# Motor_Driver.net
KiCad netlist of a schematic drawn in EAGLE
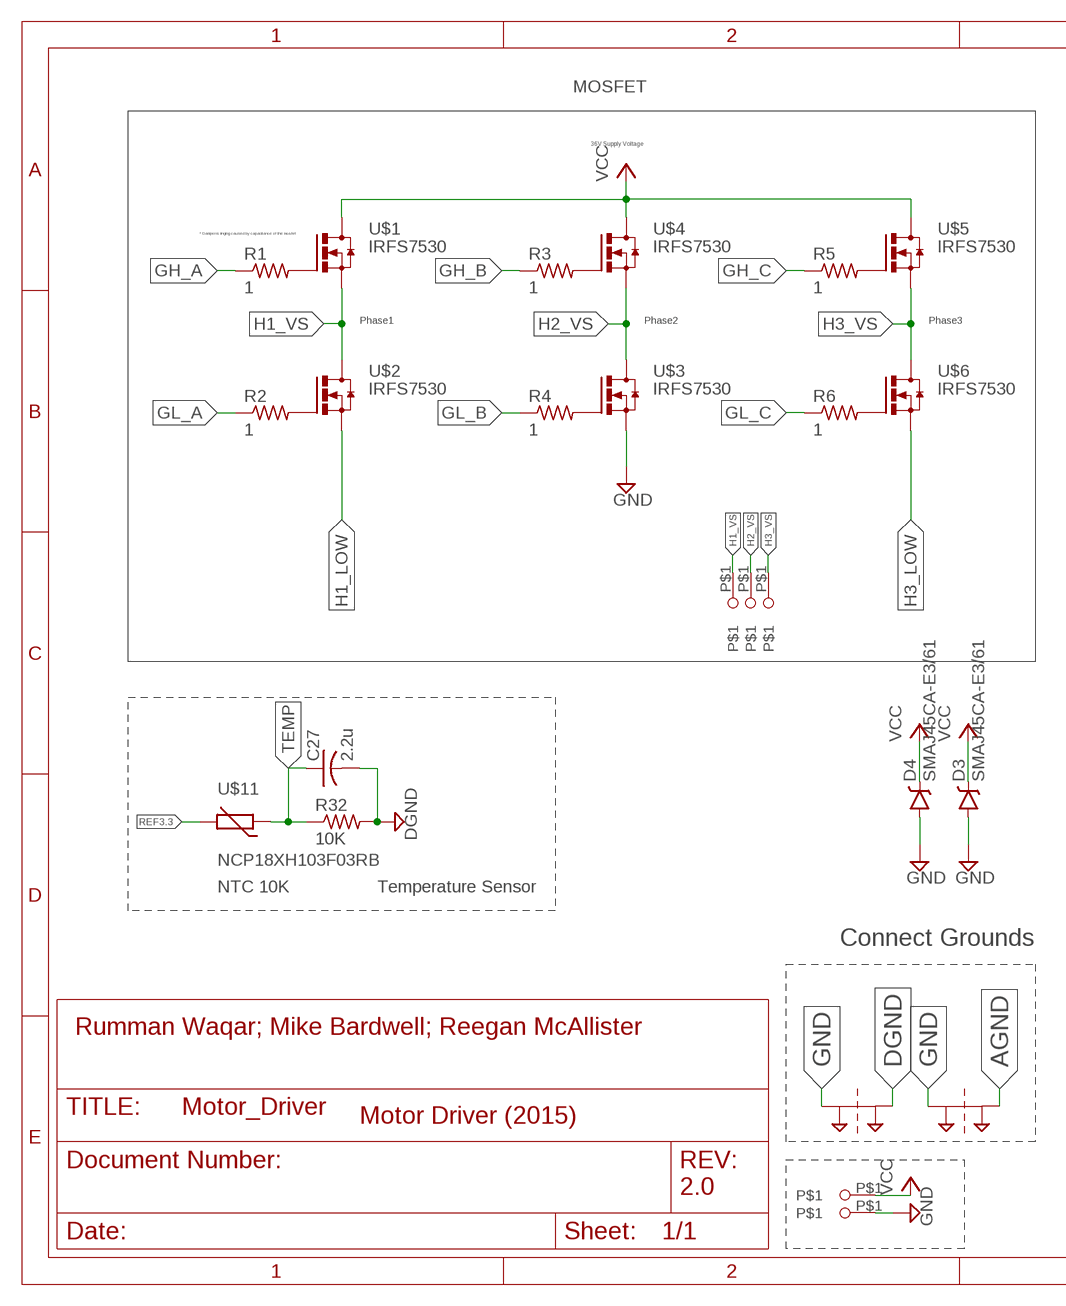
[diagram p0: schematic, sheet 1, part 1 of 2]
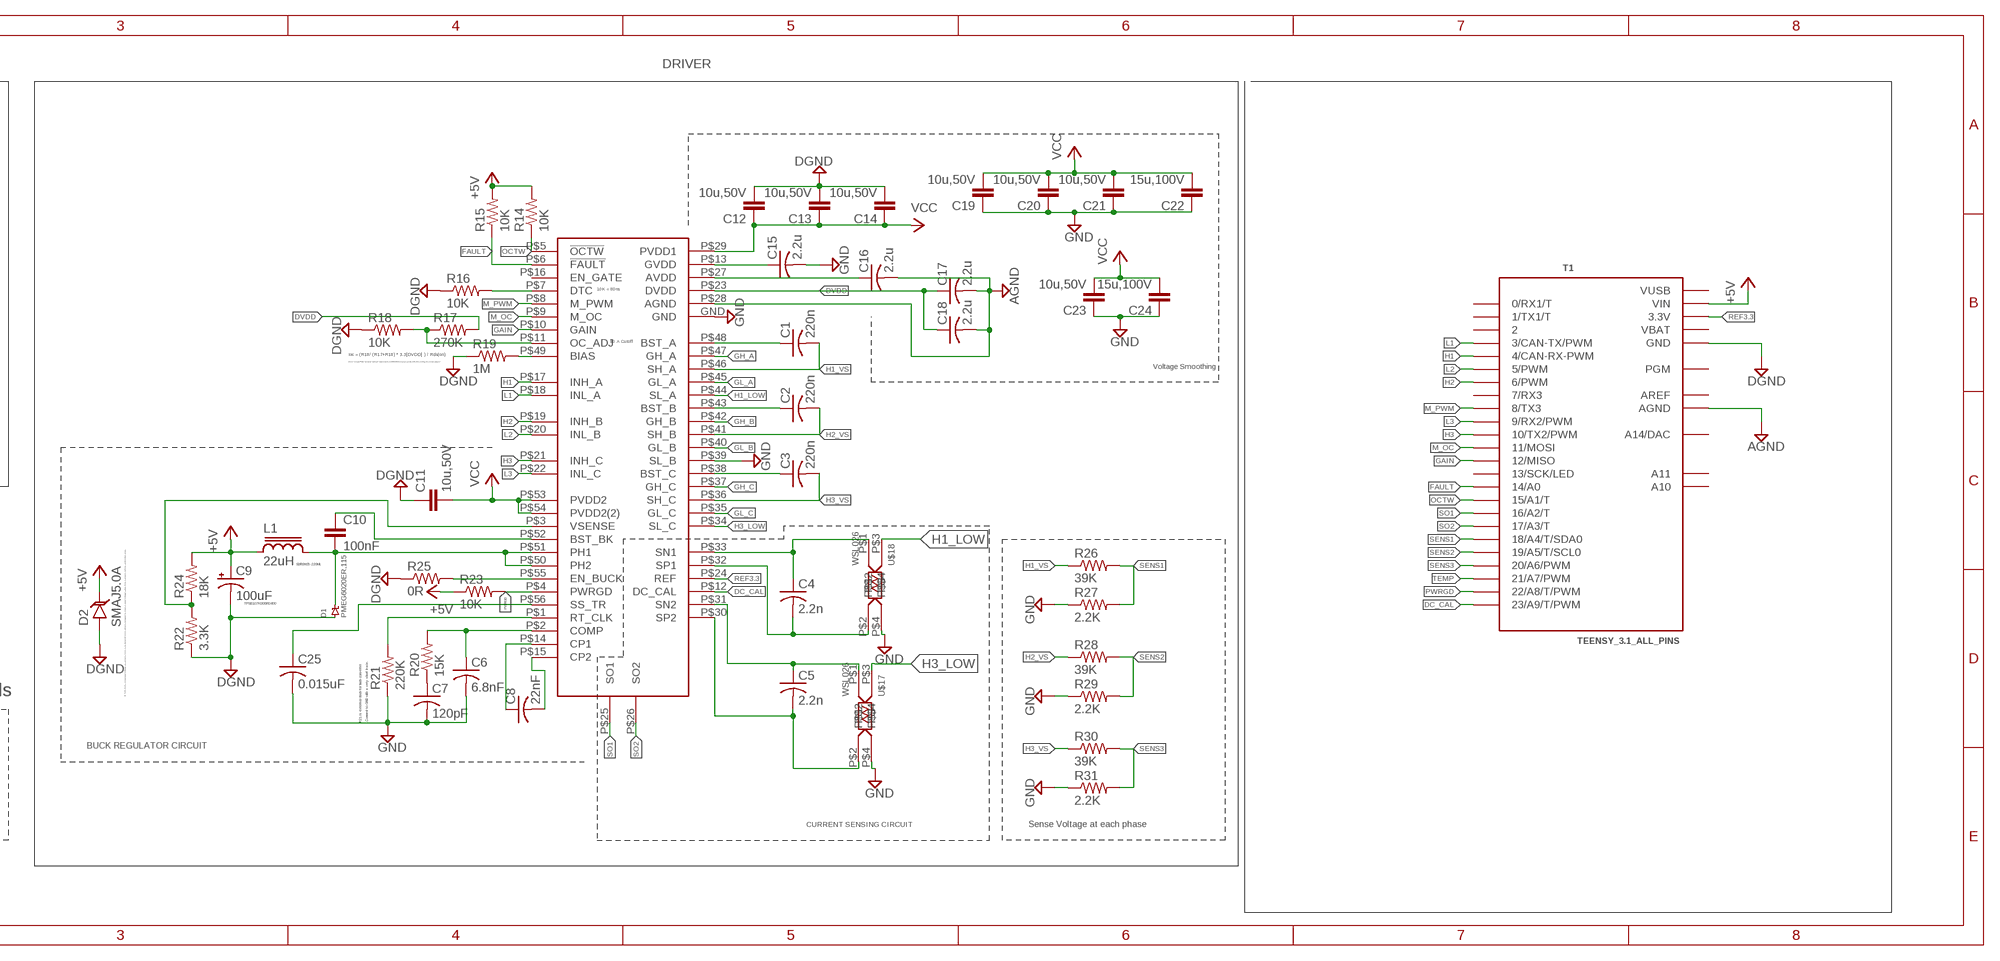
[diagram p1: schematic, sheet 1, part 2 of 2]

(export (version "E")
  (design (tool "Eeschema 10.0.6"))
  (components
    (comp (ref "C1")
      (value "220n")
      (footprint "eagle-import:C0603")
      (libsource (lib "eagle-import") (part "C-USC0603"))
    )
    (comp (ref "C2")
      (value "220n")
      (footprint "eagle-import:C0603")
      (libsource (lib "eagle-import") (part "C-USC0603"))
    )
    (comp (ref "C3")
      (value "220n")
      (footprint "eagle-import:C0603")
      (libsource (lib "eagle-import") (part "C-USC0603"))
    )
    (comp (ref "C4")
      (value "2.2n")
      (footprint "eagle-import:C0603")
      (libsource (lib "eagle-import") (part "C-USC0603"))
    )
    (comp (ref "C5")
      (value "2.2n")
      (footprint "eagle-import:C0603")
      (libsource (lib "eagle-import") (part "C-USC0603"))
    )
    (comp (ref "C6")
      (value "6.8nF")
      (footprint "eagle-import:C0603")
      (libsource (lib "eagle-import") (part "C-USC0603"))
    )
    (comp (ref "C7")
      (value "120pF")
      (footprint "eagle-import:C0603")
      (libsource (lib "eagle-import") (part "C-USC0603"))
    )
    (comp (ref "C8")
      (value "22nF")
      (footprint "eagle-import:C0603")
      (libsource (lib "eagle-import") (part "C-USC0603"))
    )
    (comp (ref "C9")
      (value "100uF")
      (footprint "eagle-import:EIA3528-KIT")
      (libsource (lib "eagle-import") (part "CAP_POL3528-KIT"))
    )
    (comp (ref "C10")
      (value "100nF")
      (footprint "eagle-import:0805")
      (libsource (lib "eagle-import") (part "CAP0805"))
    )
    (comp (ref "C11")
      (value "10u,50V")
      (footprint "eagle-import:1206")
      (libsource (lib "eagle-import") (part "CAP1206"))
    )
    (comp (ref "C12")
      (value "10u,50V")
      (footprint "eagle-import:1206")
      (libsource (lib "eagle-import") (part "CAP1206"))
    )
    (comp (ref "C13")
      (value "10u,50V")
      (footprint "eagle-import:1206")
      (libsource (lib "eagle-import") (part "CAP1206"))
    )
    (comp (ref "C14")
      (value "10u,50V")
      (footprint "eagle-import:1206")
      (libsource (lib "eagle-import") (part "CAP1206"))
    )
    (comp (ref "C15")
      (value "2.2u")
      (footprint "eagle-import:C0603")
      (libsource (lib "eagle-import") (part "C-USC0603"))
    )
    (comp (ref "C16")
      (value "2.2u")
      (footprint "eagle-import:C0603")
      (libsource (lib "eagle-import") (part "C-USC0603"))
    )
    (comp (ref "C17")
      (value "2.2u")
      (footprint "eagle-import:C0603")
      (libsource (lib "eagle-import") (part "C-USC0603"))
    )
    (comp (ref "C18")
      (value "2.2u")
      (footprint "eagle-import:C0603")
      (libsource (lib "eagle-import") (part "C-USC0603"))
    )
    (comp (ref "C19")
      (value "10u,50V")
      (footprint "eagle-import:1206")
      (libsource (lib "eagle-import") (part "CAP1206"))
    )
    (comp (ref "C20")
      (value "10u,50V")
      (footprint "eagle-import:1206")
      (libsource (lib "eagle-import") (part "CAP1206"))
    )
    (comp (ref "C21")
      (value "10u,50V")
      (footprint "eagle-import:1206")
      (libsource (lib "eagle-import") (part "CAP1206"))
    )
    (comp (ref "C22")
      (value "15u,100V")
      (footprint "eagle-import:C2220K")
      (libsource (lib "eagle-import") (part "C-EUC2220K"))
    )
    (comp (ref "C23")
      (value "10u,50V")
      (footprint "eagle-import:1206")
      (libsource (lib "eagle-import") (part "CAP1206"))
    )
    (comp (ref "C24")
      (value "15u,100V")
      (footprint "eagle-import:C2220K")
      (libsource (lib "eagle-import") (part "C-EUC2220K"))
    )
    (comp (ref "C25")
      (value "0.015uF")
      (footprint "eagle-import:C0603")
      (libsource (lib "eagle-import") (part "C-USC0603"))
    )
    (comp (ref "C27")
      (value "2.2u")
      (footprint "eagle-import:C0603")
      (libsource (lib "eagle-import") (part "C-USC0603"))
    )
    (comp (ref "D1")
      (value "PMEG6020ER,115")
      (footprint "eagle-import:SOD123W")
      (libsource (lib "eagle-import") (part "DIODE[SCHOTKY]-SOD123W"))
    )
    (comp (ref "D2")
      (value "SMAJ5.0A")
      (footprint "eagle-import:SMA-DIODE")
      (libsource (lib "eagle-import") (part "TVSSMA"))
    )
    (comp (ref "D3")
      (value "SMAJ45CA-E3/61")
      (footprint "eagle-import:SMA-DIODE")
      (libsource (lib "eagle-import") (part "MBRA140"))
    )
    (comp (ref "D4")
      (value "SMAJ45CA-E3/61")
      (footprint "eagle-import:SMA-DIODE")
      (libsource (lib "eagle-import") (part "MBRA140"))
    )
    (comp (ref "L1")
      (value "22uH")
      (footprint "eagle-import:SDR0805")
      (libsource (lib "eagle-import") (part "SDR0805"))
    )
    (comp (ref "PT1")
      (value "2PT_GND_TIE")
      (footprint "eagle-import:2PT_GND_TIE")
      (libsource (lib "eagle-import") (part "2PT_GND_TIE"))
    )
    (comp (ref "PT2")
      (value "2PT_GND_TIE")
      (footprint "eagle-import:2PT_GND_TIE")
      (libsource (lib "eagle-import") (part "2PT_GND_TIE"))
    )
    (comp (ref "R1")
      (value "1")
      (footprint "eagle-import:R0603")
      (libsource (lib "eagle-import") (part "R-US_R0603"))
    )
    (comp (ref "R2")
      (value "1")
      (footprint "eagle-import:R0603")
      (libsource (lib "eagle-import") (part "R-US_R0603"))
    )
    (comp (ref "R3")
      (value "1")
      (footprint "eagle-import:R0603")
      (libsource (lib "eagle-import") (part "R-US_R0603"))
    )
    (comp (ref "R4")
      (value "1")
      (footprint "eagle-import:R0603")
      (libsource (lib "eagle-import") (part "R-US_R0603"))
    )
    (comp (ref "R5")
      (value "1")
      (footprint "eagle-import:R0603")
      (libsource (lib "eagle-import") (part "R-US_R0603"))
    )
    (comp (ref "R6")
      (value "1")
      (footprint "eagle-import:R0603")
      (libsource (lib "eagle-import") (part "R-US_R0603"))
    )
    (comp (ref "R14")
      (value "10K")
      (footprint "eagle-import:R0603")
      (libsource (lib "eagle-import") (part "R-US_R0603"))
    )
    (comp (ref "R15")
      (value "10K")
      (footprint "eagle-import:R0603")
      (libsource (lib "eagle-import") (part "R-US_R0603"))
    )
    (comp (ref "R16")
      (value "10K")
      (footprint "eagle-import:R0603")
      (libsource (lib "eagle-import") (part "R-US_R0603"))
    )
    (comp (ref "R17")
      (value "270K")
      (footprint "eagle-import:R0603")
      (libsource (lib "eagle-import") (part "R-US_R0603"))
    )
    (comp (ref "R18")
      (value "10K")
      (footprint "eagle-import:R0603")
      (libsource (lib "eagle-import") (part "R-US_R0603"))
    )
    (comp (ref "R19")
      (value "1M")
      (footprint "eagle-import:R0603")
      (libsource (lib "eagle-import") (part "R-US_R0603"))
    )
    (comp (ref "R20")
      (value "15K")
      (footprint "eagle-import:R0603")
      (libsource (lib "eagle-import") (part "R-US_R0603"))
    )
    (comp (ref "R21")
      (value "220K")
      (footprint "eagle-import:R0603")
      (libsource (lib "eagle-import") (part "R-US_R0603"))
    )
    (comp (ref "R22")
      (value "3.3K")
      (footprint "eagle-import:R0603")
      (libsource (lib "eagle-import") (part "R-US_R0603"))
    )
    (comp (ref "R23")
      (value "10K")
      (footprint "eagle-import:R0603")
      (libsource (lib "eagle-import") (part "R-US_R0603"))
    )
    (comp (ref "R24")
      (value "18K")
      (footprint "eagle-import:R0603")
      (libsource (lib "eagle-import") (part "R-US_R0603"))
    )
    (comp (ref "R25")
      (value "0R")
      (footprint "eagle-import:R0603")
      (libsource (lib "eagle-import") (part "R-US_R0603"))
    )
    (comp (ref "R26")
      (value "39K")
      (footprint "eagle-import:R0603")
      (libsource (lib "eagle-import") (part "R-US_R0603"))
    )
    (comp (ref "R27")
      (value "2.2K")
      (footprint "eagle-import:R0603")
      (libsource (lib "eagle-import") (part "R-US_R0603"))
    )
    (comp (ref "R28")
      (value "39K")
      (footprint "eagle-import:R0603")
      (libsource (lib "eagle-import") (part "R-US_R0603"))
    )
    (comp (ref "R29")
      (value "2.2K")
      (footprint "eagle-import:R0603")
      (libsource (lib "eagle-import") (part "R-US_R0603"))
    )
    (comp (ref "R30")
      (value "39K")
      (footprint "eagle-import:R0603")
      (libsource (lib "eagle-import") (part "R-US_R0603"))
    )
    (comp (ref "R31")
      (value "2.2K")
      (footprint "eagle-import:R0603")
      (libsource (lib "eagle-import") (part "R-US_R0603"))
    )
    (comp (ref "R32")
      (value "10K")
      (footprint "eagle-import:M0805")
      (libsource (lib "eagle-import") (part "R-US_M0805"))
    )
    (comp (ref "T1")
      (value "TEENSY_3.1_ALL_PINS")
      (footprint "eagle-import:TEENSY3-ALL_PINS")
      (libsource (lib "eagle-import") (part "TEENSY_3.1_ALL_PINS"))
    )
    (comp (ref "U$1")
      (value "IRFS7530")
      (footprint "eagle-import:IRF7530_HEATSINK")
      (libsource (lib "eagle-import") (part "IRFS7530_HEATSINK"))
    )
    (comp (ref "U$2")
      (value "IRFS7530")
      (footprint "eagle-import:IRF7530_HEATSINK")
      (libsource (lib "eagle-import") (part "IRFS7530_HEATSINK"))
    )
    (comp (ref "U$3")
      (value "IRFS7530")
      (footprint "eagle-import:IRF7530_HEATSINK")
      (libsource (lib "eagle-import") (part "IRFS7530_HEATSINK"))
    )
    (comp (ref "U$4")
      (value "IRFS7530")
      (footprint "eagle-import:IRF7530_HEATSINK")
      (libsource (lib "eagle-import") (part "IRFS7530_HEATSINK"))
    )
    (comp (ref "U$5")
      (value "IRFS7530")
      (footprint "eagle-import:IRF7530_HEATSINK")
      (libsource (lib "eagle-import") (part "IRFS7530_HEATSINK"))
    )
    (comp (ref "U$6")
      (value "IRFS7530")
      (footprint "eagle-import:IRF7530_HEATSINK")
      (libsource (lib "eagle-import") (part "IRFS7530_HEATSINK"))
    )
    (comp (ref "U$7")
      (value "DRV8302")
      (footprint "eagle-import:DRV8302")
      (libsource (lib "eagle-import") (part "DRV8302"))
    )
    (comp (ref "U$11")
      (value "NCP18XH103F03RB")
      (footprint "eagle-import:R0603")
      (libsource (lib "eagle-import") (part "NCP18XH103F03RB"))
    )
    (comp (ref "U$12")
      (value "1CONN_SOLDER")
      (footprint "eagle-import:1CONN_PAD")
      (libsource (lib "eagle-import") (part "1CONN_SOLDER"))
    )
    (comp (ref "U$13")
      (value "1CONN_SOLDER")
      (footprint "eagle-import:1CONN_PAD")
      (libsource (lib "eagle-import") (part "1CONN_SOLDER"))
    )
    (comp (ref "U$14")
      (value "1CONN_SOLDER")
      (footprint "eagle-import:1CONN_PAD")
      (libsource (lib "eagle-import") (part "1CONN_SOLDER"))
    )
    (comp (ref "U$15")
      (value "1CONN_SOLDER")
      (footprint "eagle-import:1CONN_PAD")
      (libsource (lib "eagle-import") (part "1CONN_SOLDER"))
    )
    (comp (ref "U$16")
      (value "1CONN_SOLDER")
      (footprint "eagle-import:1CONN_PAD")
      (libsource (lib "eagle-import") (part "1CONN_SOLDER"))
    )
    (comp (ref "U$17")
      (value "WSL026")
      (footprint "eagle-import:REEL")
      (libsource (lib "eagle-import") (part "WSL026"))
    )
    (comp (ref "U$18")
      (value "WSL026")
      (footprint "eagle-import:REEL")
      (libsource (lib "eagle-import") (part "WSL026"))
    )
  )
  (nets
    (net (code "1") (name "+5V") (class "Default")
      (node (ref "C9") (pin "A") (pinfunction "+_A") (pintype "passive"))
      (node (ref "D2") (pin "C") (pinfunction "C_C") (pintype "passive"))
      (node (ref "L1") (pin "1") (pinfunction "1_1") (pintype "passive"))
      (node (ref "R14") (pin "2") (pinfunction "2_2") (pintype "passive"))
      (node (ref "R15") (pin "2") (pinfunction "2_2") (pintype "passive"))
      (node (ref "R23") (pin "1") (pinfunction "1_1") (pintype "passive"))
      (node (ref "R24") (pin "2") (pinfunction "2_2") (pintype "passive"))
      (node (ref "T1") (pin "VIN") (pinfunction "VIN_VIN") (pintype "power_in"))
    )
    (net (code "2") (name "/AREF") (class "Default")
      (node (ref "T1") (pin "AREF") (pinfunction "AREF_AREF") (pintype "power_in"))
    )
    (net (code "3") (name "/VBAT") (class "Default")
      (node (ref "T1") (pin "VBAT") (pinfunction "VBAT_VBAT") (pintype "power_in"))
    )
    (net (code "4") (name "/VUSB") (class "Default")
      (node (ref "T1") (pin "VUSB") (pinfunction "VUSB_VUSB") (pintype "power_in"))
    )
    (net (code "5") (name "AGND") (class "Default")
      (node (ref "C16") (pin "2") (pinfunction "2_2") (pintype "passive"))
      (node (ref "C17") (pin "2") (pinfunction "2_2") (pintype "passive"))
      (node (ref "C18") (pin "2") (pinfunction "2_2") (pintype "passive"))
      (node (ref "PT2") (pin "P$2") (pinfunction "P$2_P$2") (pintype "bidirectional"))
      (node (ref "T1") (pin "AGND") (pinfunction "AGND_AGND") (pintype "power_in"))
      (node (ref "U$7") (pin "P$28") (pinfunction "AGND_P$28") (pintype "bidirectional"))
    )
    (net (code "6") (name "DC_CAL") (class "Default")
      (node (ref "T1") (pin "23/A9") (pinfunction "23/A9/T/PWM_23/A9") (pintype "bidirectional"))
      (node (ref "U$7") (pin "P$12") (pinfunction "DC_CAL_P$12") (pintype "bidirectional"))
    )
    (net (code "7") (name "DGND") (class "Default")
      (node (ref "C11") (pin "1") (pinfunction "1_1") (pintype "passive"))
      (node (ref "C12") (pin "2") (pinfunction "2_2") (pintype "passive"))
      (node (ref "C13") (pin "2") (pinfunction "2_2") (pintype "passive"))
      (node (ref "C14") (pin "2") (pinfunction "2_2") (pintype "passive"))
      (node (ref "C27") (pin "2") (pinfunction "2_2") (pintype "passive"))
      (node (ref "C9") (pin "C") (pinfunction "-_C") (pintype "passive"))
      (node (ref "D1") (pin "P$1") (pinfunction "1_P$1") (pintype "bidirectional"))
      (node (ref "D2") (pin "A") (pinfunction "A_A") (pintype "passive"))
      (node (ref "PT1") (pin "P$2") (pinfunction "P$2_P$2") (pintype "bidirectional"))
      (node (ref "R16") (pin "1") (pinfunction "1_1") (pintype "passive"))
      (node (ref "R18") (pin "1") (pinfunction "1_1") (pintype "passive"))
      (node (ref "R19") (pin "1") (pinfunction "1_1") (pintype "passive"))
      (node (ref "R22") (pin "1") (pinfunction "1_1") (pintype "passive"))
      (node (ref "R25") (pin "1") (pinfunction "1_1") (pintype "passive"))
      (node (ref "R32") (pin "2") (pinfunction "2_2") (pintype "passive"))
      (node (ref "T1") (pin "GND") (pinfunction "GND_GND") (pintype "power_in"))
      (node (ref "T1") (pin "GND1") (pinfunction "GND_GND1") (pintype "power_in"))
    )
    (net (code "8") (name "DVDD") (class "Default")
      (node (ref "C17") (pin "1") (pinfunction "1_1") (pintype "passive"))
      (node (ref "C18") (pin "1") (pinfunction "1_1") (pintype "passive"))
      (node (ref "R17") (pin "2") (pinfunction "2_2") (pintype "passive"))
      (node (ref "U$7") (pin "P$23") (pinfunction "DVDD_P$23") (pintype "bidirectional"))
    )
    (net (code "9") (name "FAULT") (class "Default")
      (node (ref "R15") (pin "1") (pinfunction "1_1") (pintype "passive"))
      (node (ref "T1") (pin "14/A0") (pinfunction "14/A0_14/A0") (pintype "bidirectional"))
      (node (ref "U$7") (pin "P$6") (pinfunction "~{FAULT}_P$6") (pintype "bidirectional"))
    )
    (net (code "10") (name "GAIN") (class "Default")
      (node (ref "T1") (pin "12") (pinfunction "12/MISO_12") (pintype "bidirectional"))
      (node (ref "U$7") (pin "P$10") (pinfunction "GAIN_P$10") (pintype "bidirectional"))
    )
    (net (code "11") (name "GH_A") (class "Default")
      (node (ref "R1") (pin "1") (pinfunction "1_1") (pintype "passive"))
      (node (ref "U$7") (pin "P$47") (pinfunction "GH_A_P$47") (pintype "bidirectional"))
    )
    (net (code "12") (name "GH_B") (class "Default")
      (node (ref "R3") (pin "1") (pinfunction "1_1") (pintype "passive"))
      (node (ref "U$7") (pin "P$42") (pinfunction "GH_B_P$42") (pintype "bidirectional"))
    )
    (net (code "13") (name "GH_C") (class "Default")
      (node (ref "R5") (pin "1") (pinfunction "1_1") (pintype "passive"))
      (node (ref "U$7") (pin "P$37") (pinfunction "GH_C_P$37") (pintype "bidirectional"))
    )
    (net (code "14") (name "GL_A") (class "Default")
      (node (ref "R2") (pin "1") (pinfunction "1_1") (pintype "passive"))
      (node (ref "U$7") (pin "P$45") (pinfunction "GL_A_P$45") (pintype "bidirectional"))
    )
    (net (code "15") (name "GL_B") (class "Default")
      (node (ref "R4") (pin "1") (pinfunction "1_1") (pintype "passive"))
      (node (ref "U$7") (pin "P$40") (pinfunction "GL_B_P$40") (pintype "bidirectional"))
    )
    (net (code "16") (name "GL_C") (class "Default")
      (node (ref "R6") (pin "1") (pinfunction "1_1") (pintype "passive"))
      (node (ref "U$7") (pin "P$35") (pinfunction "GL_C_P$35") (pintype "bidirectional"))
    )
    (net (code "17") (name "GND") (class "Default")
      (node (ref "C15") (pin "2") (pinfunction "2_2") (pintype "passive"))
      (node (ref "C19") (pin "1") (pinfunction "1_1") (pintype "passive"))
      (node (ref "C20") (pin "1") (pinfunction "1_1") (pintype "passive"))
      (node (ref "C21") (pin "1") (pinfunction "1_1") (pintype "passive"))
      (node (ref "C22") (pin "1") (pinfunction "1_1") (pintype "passive"))
      (node (ref "C23") (pin "1") (pinfunction "1_1") (pintype "passive"))
      (node (ref "C24") (pin "1") (pinfunction "1_1") (pintype "passive"))
      (node (ref "C25") (pin "2") (pinfunction "2_2") (pintype "passive"))
      (node (ref "C6") (pin "2") (pinfunction "2_2") (pintype "passive"))
      (node (ref "C7") (pin "2") (pinfunction "2_2") (pintype "passive"))
      (node (ref "D3") (pin "A") (pinfunction "A_A") (pintype "passive"))
      (node (ref "D4") (pin "A") (pinfunction "A_A") (pintype "passive"))
      (node (ref "PT1") (pin "P$1") (pinfunction "P$1_P$1") (pintype "bidirectional"))
      (node (ref "PT2") (pin "P$1") (pinfunction "P$1_P$1") (pintype "bidirectional"))
      (node (ref "R21") (pin "1") (pinfunction "1_1") (pintype "passive"))
      (node (ref "R27") (pin "1") (pinfunction "1_1") (pintype "passive"))
      (node (ref "R29") (pin "1") (pinfunction "1_1") (pintype "passive"))
      (node (ref "R31") (pin "1") (pinfunction "1_1") (pintype "passive"))
      (node (ref "U$16") (pin "P$1") (pinfunction "P$1_P$1") (pintype "bidirectional"))
      (node (ref "U$17") (pin "P$4") (pinfunction "P$4_P$4") (pintype "bidirectional"))
      (node (ref "U$18") (pin "P$4") (pinfunction "P$4_P$4") (pintype "bidirectional"))
      (node (ref "U$3") (pin "S1") (pinfunction "S_S1") (pintype "passive"))
      (node (ref "U$3") (pin "S2") (pinfunction "S_S2") (pintype "passive"))
      (node (ref "U$3") (pin "S3") (pinfunction "S_S3") (pintype "passive"))
      (node (ref "U$3") (pin "S4") (pinfunction "S_S4") (pintype "passive"))
      (node (ref "U$3") (pin "S5") (pinfunction "S_S5") (pintype "passive"))
      (node (ref "U$7") (pin "GND") (pinfunction "GND_GND") (pintype "bidirectional"))
      (node (ref "U$7") (pin "P$39") (pinfunction "SL_B_P$39") (pintype "bidirectional"))
    )
    (net (code "18") (name "H1") (class "Default")
      (node (ref "T1") (pin "4") (pinfunction "4/CAN-RX-PWM_4") (pintype "bidirectional"))
      (node (ref "U$7") (pin "P$17") (pinfunction "INH_A_P$17") (pintype "bidirectional"))
    )
    (net (code "19") (name "H1_LOW") (class "Default")
      (node (ref "U$18") (pin "P$3") (pinfunction "P$3_P$3") (pintype "bidirectional"))
      (node (ref "U$2") (pin "S1") (pinfunction "S_S1") (pintype "passive"))
      (node (ref "U$2") (pin "S2") (pinfunction "S_S2") (pintype "passive"))
      (node (ref "U$2") (pin "S3") (pinfunction "S_S3") (pintype "passive"))
      (node (ref "U$2") (pin "S4") (pinfunction "S_S4") (pintype "passive"))
      (node (ref "U$2") (pin "S5") (pinfunction "S_S5") (pintype "passive"))
      (node (ref "U$7") (pin "P$44") (pinfunction "SL_A_P$44") (pintype "bidirectional"))
    )
    (net (code "20") (name "H1_VS") (class "Default")
      (node (ref "C1") (pin "2") (pinfunction "2_2") (pintype "passive"))
      (node (ref "R26") (pin "1") (pinfunction "1_1") (pintype "passive"))
      (node (ref "U$1") (pin "S1") (pinfunction "S_S1") (pintype "passive"))
      (node (ref "U$1") (pin "S2") (pinfunction "S_S2") (pintype "passive"))
      (node (ref "U$1") (pin "S3") (pinfunction "S_S3") (pintype "passive"))
      (node (ref "U$1") (pin "S4") (pinfunction "S_S4") (pintype "passive"))
      (node (ref "U$1") (pin "S5") (pinfunction "S_S5") (pintype "passive"))
      (node (ref "U$14") (pin "P$1") (pinfunction "P$1_P$1") (pintype "bidirectional"))
      (node (ref "U$2") (pin "D1") (pinfunction "D_D1") (pintype "passive"))
      (node (ref "U$7") (pin "P$46") (pinfunction "SH_A_P$46") (pintype "bidirectional"))
    )
    (net (code "21") (name "H2") (class "Default")
      (node (ref "T1") (pin "6") (pinfunction "6/PWM_6") (pintype "bidirectional"))
      (node (ref "U$7") (pin "P$19") (pinfunction "INH_B_P$19") (pintype "bidirectional"))
    )
    (net (code "22") (name "H2_VS") (class "Default")
      (node (ref "C2") (pin "2") (pinfunction "2_2") (pintype "passive"))
      (node (ref "R28") (pin "1") (pinfunction "1_1") (pintype "passive"))
      (node (ref "U$13") (pin "P$1") (pinfunction "P$1_P$1") (pintype "bidirectional"))
      (node (ref "U$3") (pin "D1") (pinfunction "D_D1") (pintype "passive"))
      (node (ref "U$4") (pin "S1") (pinfunction "S_S1") (pintype "passive"))
      (node (ref "U$4") (pin "S2") (pinfunction "S_S2") (pintype "passive"))
      (node (ref "U$4") (pin "S3") (pinfunction "S_S3") (pintype "passive"))
      (node (ref "U$4") (pin "S4") (pinfunction "S_S4") (pintype "passive"))
      (node (ref "U$4") (pin "S5") (pinfunction "S_S5") (pintype "passive"))
      (node (ref "U$7") (pin "P$41") (pinfunction "SH_B_P$41") (pintype "bidirectional"))
    )
    (net (code "23") (name "H3") (class "Default")
      (node (ref "T1") (pin "10") (pinfunction "10/TX2/PWM_10") (pintype "bidirectional"))
      (node (ref "U$7") (pin "P$21") (pinfunction "INH_C_P$21") (pintype "bidirectional"))
    )
    (net (code "24") (name "H3_LOW") (class "Default")
      (node (ref "U$17") (pin "P$3") (pinfunction "P$3_P$3") (pintype "bidirectional"))
      (node (ref "U$6") (pin "S1") (pinfunction "S_S1") (pintype "passive"))
      (node (ref "U$6") (pin "S2") (pinfunction "S_S2") (pintype "passive"))
      (node (ref "U$6") (pin "S3") (pinfunction "S_S3") (pintype "passive"))
      (node (ref "U$6") (pin "S4") (pinfunction "S_S4") (pintype "passive"))
      (node (ref "U$6") (pin "S5") (pinfunction "S_S5") (pintype "passive"))
      (node (ref "U$7") (pin "P$34") (pinfunction "SL_C_P$34") (pintype "bidirectional"))
    )
    (net (code "25") (name "H3_VS") (class "Default")
      (node (ref "C3") (pin "2") (pinfunction "2_2") (pintype "passive"))
      (node (ref "R30") (pin "1") (pinfunction "1_1") (pintype "passive"))
      (node (ref "U$12") (pin "P$1") (pinfunction "P$1_P$1") (pintype "bidirectional"))
      (node (ref "U$5") (pin "S1") (pinfunction "S_S1") (pintype "passive"))
      (node (ref "U$5") (pin "S2") (pinfunction "S_S2") (pintype "passive"))
      (node (ref "U$5") (pin "S3") (pinfunction "S_S3") (pintype "passive"))
      (node (ref "U$5") (pin "S4") (pinfunction "S_S4") (pintype "passive"))
      (node (ref "U$5") (pin "S5") (pinfunction "S_S5") (pintype "passive"))
      (node (ref "U$6") (pin "D1") (pinfunction "D_D1") (pintype "passive"))
      (node (ref "U$7") (pin "P$36") (pinfunction "SH_C_P$36") (pintype "bidirectional"))
    )
    (net (code "26") (name "L1") (class "Default")
      (node (ref "T1") (pin "3") (pinfunction "3/CAN-TX/PWM_3") (pintype "bidirectional"))
      (node (ref "U$7") (pin "P$18") (pinfunction "INL_A_P$18") (pintype "bidirectional"))
    )
    (net (code "27") (name "L2") (class "Default")
      (node (ref "T1") (pin "5") (pinfunction "5/PWM_5") (pintype "bidirectional"))
      (node (ref "U$7") (pin "P$20") (pinfunction "INL_B_P$20") (pintype "bidirectional"))
    )
    (net (code "28") (name "L3") (class "Default")
      (node (ref "T1") (pin "9") (pinfunction "9/RX2/PWM_9") (pintype "bidirectional"))
      (node (ref "U$7") (pin "P$22") (pinfunction "INL_C_P$22") (pintype "bidirectional"))
    )
    (net (code "29") (name "M_OC") (class "Default")
      (node (ref "T1") (pin "11") (pinfunction "11/MOSI_11") (pintype "bidirectional"))
      (node (ref "U$7") (pin "P$9") (pinfunction "M_OC_P$9") (pintype "bidirectional"))
    )
    (net (code "30") (name "M_PWM") (class "Default")
      (node (ref "T1") (pin "8") (pinfunction "8/TX3_8") (pintype "bidirectional"))
      (node (ref "U$7") (pin "P$8") (pinfunction "M_PWM_P$8") (pintype "bidirectional"))
    )
    (net (code "31") (name "Net-(C7-Pad1)") (class "Default")
      (node (ref "C7") (pin "1") (pinfunction "1_1") (pintype "passive"))
      (node (ref "R20") (pin "1") (pinfunction "1_1") (pintype "passive"))
    )
    (net (code "32") (name "Net-(D1-2)") (class "Default")
      (node (ref "C10") (pin "2") (pinfunction "2_2") (pintype "passive"))
      (node (ref "D1") (pin "P$2") (pinfunction "2_P$2") (pintype "bidirectional"))
      (node (ref "L1") (pin "2") (pinfunction "2_2") (pintype "passive"))
      (node (ref "U$7") (pin "P$50") (pinfunction "PH2_P$50") (pintype "bidirectional"))
      (node (ref "U$7") (pin "P$51") (pinfunction "PH1_P$51") (pintype "bidirectional"))
    )
    (net (code "33") (name "Net-(U$1-G)") (class "Default")
      (node (ref "R1") (pin "2") (pinfunction "2_2") (pintype "passive"))
      (node (ref "U$1") (pin "G1") (pinfunction "G_G1") (pintype "passive"))
    )
    (net (code "34") (name "Net-(U$2-G)") (class "Default")
      (node (ref "R2") (pin "2") (pinfunction "2_2") (pintype "passive"))
      (node (ref "U$2") (pin "G1") (pinfunction "G_G1") (pintype "passive"))
    )
    (net (code "35") (name "Net-(U$3-G)") (class "Default")
      (node (ref "R4") (pin "2") (pinfunction "2_2") (pintype "passive"))
      (node (ref "U$3") (pin "G1") (pinfunction "G_G1") (pintype "passive"))
    )
    (net (code "36") (name "Net-(U$4-G)") (class "Default")
      (node (ref "R3") (pin "2") (pinfunction "2_2") (pintype "passive"))
      (node (ref "U$4") (pin "G1") (pinfunction "G_G1") (pintype "passive"))
    )
    (net (code "37") (name "Net-(U$5-G)") (class "Default")
      (node (ref "R5") (pin "2") (pinfunction "2_2") (pintype "passive"))
      (node (ref "U$5") (pin "G1") (pinfunction "G_G1") (pintype "passive"))
    )
    (net (code "38") (name "Net-(U$6-G)") (class "Default")
      (node (ref "R6") (pin "2") (pinfunction "2_2") (pintype "passive"))
      (node (ref "U$6") (pin "G1") (pinfunction "G_G1") (pintype "passive"))
    )
    (net (code "39") (name "Net-(U$7-AVDD)") (class "Default")
      (node (ref "C16") (pin "1") (pinfunction "1_1") (pintype "passive"))
      (node (ref "U$7") (pin "P$27") (pinfunction "AVDD_P$27") (pintype "bidirectional"))
    )
    (net (code "40") (name "Net-(U$7-BIAS)") (class "Default")
      (node (ref "R19") (pin "2") (pinfunction "2_2") (pintype "passive"))
      (node (ref "U$7") (pin "P$49") (pinfunction "BIAS_P$49") (pintype "bidirectional"))
    )
    (net (code "41") (name "Net-(U$7-BST_A)") (class "Default")
      (node (ref "C1") (pin "1") (pinfunction "1_1") (pintype "passive"))
      (node (ref "U$7") (pin "P$48") (pinfunction "BST_A_P$48") (pintype "bidirectional"))
    )
    (net (code "42") (name "Net-(U$7-BST_B)") (class "Default")
      (node (ref "C2") (pin "1") (pinfunction "1_1") (pintype "passive"))
      (node (ref "U$7") (pin "P$43") (pinfunction "BST_B_P$43") (pintype "bidirectional"))
    )
    (net (code "43") (name "Net-(U$7-BST_BK)") (class "Default")
      (node (ref "C10") (pin "1") (pinfunction "1_1") (pintype "passive"))
      (node (ref "U$7") (pin "P$52") (pinfunction "BST_BK_P$52") (pintype "bidirectional"))
    )
    (net (code "44") (name "Net-(U$7-BST_C)") (class "Default")
      (node (ref "C3") (pin "1") (pinfunction "1_1") (pintype "passive"))
      (node (ref "U$7") (pin "P$38") (pinfunction "BST_C_P$38") (pintype "bidirectional"))
    )
    (net (code "45") (name "Net-(U$7-COMP)") (class "Default")
      (node (ref "C6") (pin "1") (pinfunction "1_1") (pintype "passive"))
      (node (ref "R20") (pin "2") (pinfunction "2_2") (pintype "passive"))
      (node (ref "U$7") (pin "P$2") (pinfunction "COMP_P$2") (pintype "bidirectional"))
    )
    (net (code "46") (name "Net-(U$7-CP1)") (class "Default")
      (node (ref "C8") (pin "1") (pinfunction "1_1") (pintype "passive"))
      (node (ref "U$7") (pin "P$14") (pinfunction "CP1_P$14") (pintype "bidirectional"))
    )
    (net (code "47") (name "Net-(U$7-CP2)") (class "Default")
      (node (ref "C8") (pin "2") (pinfunction "2_2") (pintype "passive"))
      (node (ref "U$7") (pin "P$15") (pinfunction "CP2_P$15") (pintype "bidirectional"))
    )
    (net (code "48") (name "Net-(U$7-DTC)") (class "Default")
      (node (ref "R16") (pin "2") (pinfunction "2_2") (pintype "passive"))
      (node (ref "U$7") (pin "P$7") (pinfunction "DTC_P$7") (pintype "bidirectional"))
    )
    (net (code "49") (name "Net-(U$7-EN_BUCK)") (class "Default")
      (node (ref "R25") (pin "2") (pinfunction "2_2") (pintype "passive"))
      (node (ref "U$7") (pin "P$55") (pinfunction "EN_BUCK_P$55") (pintype "bidirectional"))
    )
    (net (code "50") (name "Net-(U$7-GVDD)") (class "Default")
      (node (ref "C15") (pin "1") (pinfunction "1_1") (pintype "passive"))
      (node (ref "U$7") (pin "P$13") (pinfunction "GVDD_P$13") (pintype "bidirectional"))
    )
    (net (code "51") (name "Net-(U$7-OC_ADJ)") (class "Default")
      (node (ref "R17") (pin "1") (pinfunction "1_1") (pintype "passive"))
      (node (ref "R18") (pin "2") (pinfunction "2_2") (pintype "passive"))
      (node (ref "U$7") (pin "P$11") (pinfunction "OC_ADJ_P$11") (pintype "bidirectional"))
    )
    (net (code "52") (name "Net-(U$7-RT_CLK)") (class "Default")
      (node (ref "R21") (pin "2") (pinfunction "2_2") (pintype "passive"))
      (node (ref "U$7") (pin "P$1") (pinfunction "RT_CLK_P$1") (pintype "bidirectional"))
    )
    (net (code "53") (name "Net-(U$7-SN1)") (class "Default")
      (node (ref "C4") (pin "1") (pinfunction "1_1") (pintype "passive"))
      (node (ref "U$18") (pin "P$1") (pinfunction "P$1_P$1") (pintype "bidirectional"))
      (node (ref "U$7") (pin "P$33") (pinfunction "SN1_P$33") (pintype "bidirectional"))
    )
    (net (code "54") (name "Net-(U$7-SN2)") (class "Default")
      (node (ref "C5") (pin "1") (pinfunction "1_1") (pintype "passive"))
      (node (ref "U$17") (pin "P$1") (pinfunction "P$1_P$1") (pintype "bidirectional"))
      (node (ref "U$7") (pin "P$31") (pinfunction "SN2_P$31") (pintype "bidirectional"))
    )
    (net (code "55") (name "Net-(U$7-SP1)") (class "Default")
      (node (ref "C4") (pin "2") (pinfunction "2_2") (pintype "passive"))
      (node (ref "U$18") (pin "P$2") (pinfunction "P$2_P$2") (pintype "bidirectional"))
      (node (ref "U$7") (pin "P$32") (pinfunction "SP1_P$32") (pintype "bidirectional"))
    )
    (net (code "56") (name "Net-(U$7-SP2)") (class "Default")
      (node (ref "C5") (pin "2") (pinfunction "2_2") (pintype "passive"))
      (node (ref "U$17") (pin "P$2") (pinfunction "P$2_P$2") (pintype "bidirectional"))
      (node (ref "U$7") (pin "P$30") (pinfunction "SP2_P$30") (pintype "bidirectional"))
    )
    (net (code "57") (name "Net-(U$7-SS_TR)") (class "Default")
      (node (ref "C25") (pin "1") (pinfunction "1_1") (pintype "passive"))
      (node (ref "U$7") (pin "P$56") (pinfunction "SS_TR_P$56") (pintype "bidirectional"))
    )
    (net (code "58") (name "Net-(U$7-VSENSE)") (class "Default")
      (node (ref "R22") (pin "2") (pinfunction "2_2") (pintype "passive"))
      (node (ref "R24") (pin "1") (pinfunction "1_1") (pintype "passive"))
      (node (ref "U$7") (pin "P$3") (pinfunction "VSENSE_P$3") (pintype "bidirectional"))
    )
    (net (code "59") (name "OCTW") (class "Default")
      (node (ref "R14") (pin "1") (pinfunction "1_1") (pintype "passive"))
      (node (ref "T1") (pin "15/A1") (pinfunction "15/A1/T_15/A1") (pintype "bidirectional"))
      (node (ref "U$7") (pin "P$5") (pinfunction "~{OCTW}_P$5") (pintype "bidirectional"))
    )
    (net (code "60") (name "PWRGD") (class "Default")
      (node (ref "R23") (pin "2") (pinfunction "2_2") (pintype "passive"))
      (node (ref "T1") (pin "22/A8") (pinfunction "22/A8/T/PWM_22/A8") (pintype "bidirectional"))
      (node (ref "U$7") (pin "P$4") (pinfunction "PWRGD_P$4") (pintype "bidirectional"))
    )
    (net (code "61") (name "REF3.3") (class "Default")
      (node (ref "T1") (pin "3.3V") (pinfunction "3.3V_3.3V") (pintype "power_in"))
      (node (ref "T1") (pin "3.3V1") (pinfunction "3.3V_3.3V1") (pintype "power_in"))
      (node (ref "U$11") (pin "2") (pinfunction "2_2") (pintype "passive"))
      (node (ref "U$7") (pin "P$24") (pinfunction "REF_P$24") (pintype "bidirectional"))
    )
    (net (code "62") (name "SENS1") (class "Default")
      (node (ref "R26") (pin "2") (pinfunction "2_2") (pintype "passive"))
      (node (ref "R27") (pin "2") (pinfunction "2_2") (pintype "passive"))
      (node (ref "T1") (pin "18/A4") (pinfunction "18/A4/T/SDA0_18/A4") (pintype "bidirectional"))
    )
    (net (code "63") (name "SENS2") (class "Default")
      (node (ref "R28") (pin "2") (pinfunction "2_2") (pintype "passive"))
      (node (ref "R29") (pin "2") (pinfunction "2_2") (pintype "passive"))
      (node (ref "T1") (pin "19/A5") (pinfunction "19/A5/T/SCL0_19/A5") (pintype "bidirectional"))
    )
    (net (code "64") (name "SENS3") (class "Default")
      (node (ref "R30") (pin "2") (pinfunction "2_2") (pintype "passive"))
      (node (ref "R31") (pin "2") (pinfunction "2_2") (pintype "passive"))
      (node (ref "T1") (pin "20/A6") (pinfunction "20/A6/PWM_20/A6") (pintype "bidirectional"))
    )
    (net (code "65") (name "SO1") (class "Default")
      (node (ref "T1") (pin "16/A2") (pinfunction "16/A2/T_16/A2") (pintype "bidirectional"))
      (node (ref "U$7") (pin "P$25") (pinfunction "SO1_P$25") (pintype "bidirectional"))
    )
    (net (code "66") (name "SO2") (class "Default")
      (node (ref "T1") (pin "17/A3") (pinfunction "17/A3/T_17/A3") (pintype "bidirectional"))
      (node (ref "U$7") (pin "P$26") (pinfunction "SO2_P$26") (pintype "bidirectional"))
    )
    (net (code "67") (name "TEMP") (class "Default")
      (node (ref "C27") (pin "1") (pinfunction "1_1") (pintype "passive"))
      (node (ref "R32") (pin "1") (pinfunction "1_1") (pintype "passive"))
      (node (ref "T1") (pin "21/A7") (pinfunction "21/A7/PWM_21/A7") (pintype "bidirectional"))
      (node (ref "U$11") (pin "1") (pinfunction "1_1") (pintype "passive"))
    )
    (net (code "68") (name "VCC") (class "Default")
      (node (ref "C11") (pin "2") (pinfunction "2_2") (pintype "passive"))
      (node (ref "C12") (pin "1") (pinfunction "1_1") (pintype "passive"))
      (node (ref "C13") (pin "1") (pinfunction "1_1") (pintype "passive"))
      (node (ref "C14") (pin "1") (pinfunction "1_1") (pintype "passive"))
      (node (ref "C19") (pin "2") (pinfunction "2_2") (pintype "passive"))
      (node (ref "C20") (pin "2") (pinfunction "2_2") (pintype "passive"))
      (node (ref "C21") (pin "2") (pinfunction "2_2") (pintype "passive"))
      (node (ref "C22") (pin "2") (pinfunction "2_2") (pintype "passive"))
      (node (ref "C23") (pin "2") (pinfunction "2_2") (pintype "passive"))
      (node (ref "C24") (pin "2") (pinfunction "2_2") (pintype "passive"))
      (node (ref "D3") (pin "C") (pinfunction "C_C") (pintype "passive"))
      (node (ref "D4") (pin "C") (pinfunction "C_C") (pintype "passive"))
      (node (ref "U$1") (pin "D1") (pinfunction "D_D1") (pintype "passive"))
      (node (ref "U$15") (pin "P$1") (pinfunction "P$1_P$1") (pintype "bidirectional"))
      (node (ref "U$4") (pin "D1") (pinfunction "D_D1") (pintype "passive"))
      (node (ref "U$5") (pin "D1") (pinfunction "D_D1") (pintype "passive"))
      (node (ref "U$7") (pin "P$29") (pinfunction "PVDD1_P$29") (pintype "bidirectional"))
      (node (ref "U$7") (pin "P$53") (pinfunction "PVDD2_P$53") (pintype "bidirectional"))
      (node (ref "U$7") (pin "P$54") (pinfunction "PVDD2(2)_P$54") (pintype "bidirectional"))
    )
    (net (code "69") (name "unconnected-(T1-0{slash}RX1{slash}T-Pad0)") (class "Default")
      (node (ref "T1") (pin "0") (pinfunction "0/RX1/T_0") (pintype "bidirectional"))
    )
    (net (code "70") (name "unconnected-(T1-1{slash}TX1{slash}T-Pad1)") (class "Default")
      (node (ref "T1") (pin "1") (pinfunction "1/TX1/T_1") (pintype "bidirectional"))
    )
    (net (code "71") (name "unconnected-(T1-7{slash}RX3-Pad7)") (class "Default")
      (node (ref "T1") (pin "7") (pinfunction "7/RX3_7") (pintype "bidirectional"))
    )
    (net (code "72") (name "unconnected-(T1-13{slash}SCK{slash}LED-Pad13)") (class "Default")
      (node (ref "T1") (pin "13") (pinfunction "13/SCK/LED_13") (pintype "bidirectional"))
    )
    (net (code "73") (name "unconnected-(T1-A14{slash}DAC-PadRESET{slash}DAC)") (class "Default")
      (node (ref "T1") (pin "RESET/DAC") (pinfunction "A14/DAC_RESET/DAC") (pintype "bidirectional"))
    )
    (net (code "74") (name "unconnected-(T1-Pad2)") (class "Default")
      (node (ref "T1") (pin "2") (pinfunction "2_2") (pintype "bidirectional"))
    )
    (net (code "75") (name "unconnected-(T1-PadA10)") (class "Default")
      (node (ref "T1") (pin "A10") (pinfunction "A10_A10") (pintype "bidirectional"))
    )
    (net (code "76") (name "unconnected-(T1-PadA11)") (class "Default")
      (node (ref "T1") (pin "A11") (pinfunction "A11_A11") (pintype "bidirectional"))
    )
    (net (code "77") (name "unconnected-(T1-PadPGM)") (class "Default")
      (node (ref "T1") (pin "PGM") (pinfunction "PGM_PGM") (pintype "bidirectional"))
    )
    (net (code "78") (name "unconnected-(U$7-EN_GATE-PadP$16)") (class "Default")
      (node (ref "U$7") (pin "P$16") (pinfunction "EN_GATE_P$16") (pintype "bidirectional"))
    )
  )
)
